# STM32F103.net
KiCad netlist of a schematic drawn in Altium Designer
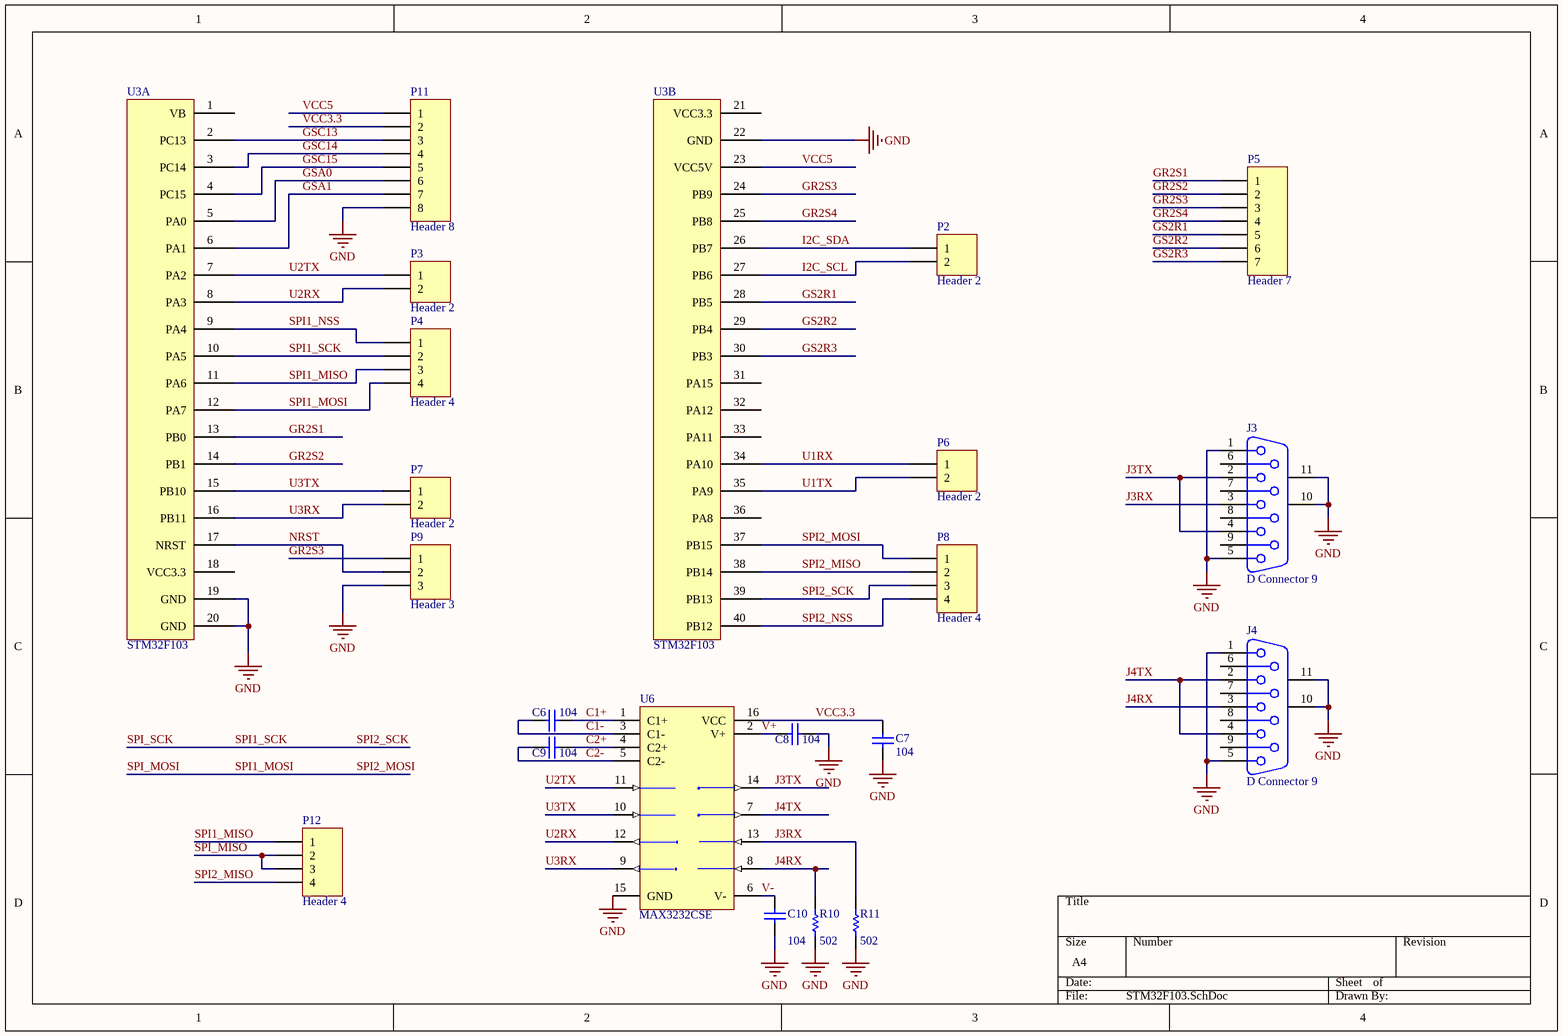
[diagram p0: STM32F103.SchDoc]

(export (version "E")
  (design (tool "Eeschema 10.0.6"))
  (components
    (comp (ref "C6")
      (value "104")
      (footprint "CAPC3216L")
      (description "Capacitor (Semiconductor SIM Model)")
      (fields (field (name "Comment") "Cap Semi") (field (name "PUBLISHER") "Altium Limited"))
      (libsource (lib "Miscellaneous Devices") (part "Cap Semi"))
    )
    (comp (ref "C7")
      (value "104")
      (footprint "CAPC3216L")
      (description "Capacitor (Semiconductor SIM Model)")
      (fields (field (name "Comment") "Cap Semi") (field (name "PUBLISHER") "Altium Limited"))
      (libsource (lib "Miscellaneous Devices") (part "Cap Semi"))
    )
    (comp (ref "C8")
      (value "104")
      (footprint "CAPC3216L")
      (description "Capacitor (Semiconductor SIM Model)")
      (fields (field (name "Comment") "Cap Semi") (field (name "PUBLISHER") "Altium Limited"))
      (libsource (lib "Miscellaneous Devices") (part "Cap Semi"))
    )
    (comp (ref "C9")
      (value "104")
      (footprint "CAPC3216L")
      (description "Capacitor (Semiconductor SIM Model)")
      (fields (field (name "Comment") "Cap Semi") (field (name "PUBLISHER") "Altium Limited"))
      (libsource (lib "Miscellaneous Devices") (part "Cap Semi"))
    )
    (comp (ref "C10")
      (value "104")
      (footprint "CAPC3216L")
      (description "Capacitor (Semiconductor SIM Model)")
      (fields (field (name "Comment") "Cap Semi") (field (name "PUBLISHER") "Altium Limited"))
      (libsource (lib "Miscellaneous Devices") (part "Cap Semi"))
    )
    (comp (ref "J3")
      (value "D Connector 9")
      (footprint "DSUB1.385-2H9")
      (description "Receptacle Assembly, 9 Position, Right Angle")
      (fields (field (name "PUBLISHER") "Altium Limited"))
      (libsource (lib "Miscellaneous Connectors") (part "D Connector 9"))
    )
    (comp (ref "J4")
      (value "D Connector 9")
      (footprint "DSUB1.385-2H9")
      (description "Receptacle Assembly, 9 Position, Right Angle")
      (fields (field (name "PUBLISHER") "Altium Limited"))
      (libsource (lib "Miscellaneous Connectors") (part "D Connector 9"))
    )
    (comp (ref "P2")
      (value "Header 2")
      (footprint "HDR1X2")
      (description "Header, 2-Pin")
      (fields (field (name "PUBLISHER") "Altium Limited"))
      (libsource (lib "Miscellaneous Connectors") (part "Header 2"))
    )
    (comp (ref "P3")
      (value "Header 2")
      (footprint "HDR1X2")
      (description "Header, 2-Pin")
      (fields (field (name "PUBLISHER") "Altium Limited"))
      (libsource (lib "Miscellaneous Connectors") (part "Header 2"))
    )
    (comp (ref "P4")
      (value "Header 4")
      (footprint "HDR1X4")
      (description "Header, 4-Pin")
      (fields (field (name "PUBLISHER") "Altium Limited"))
      (libsource (lib "Miscellaneous Connectors") (part "Header 4"))
    )
    (comp (ref "P5")
      (value "Header 7")
      (footprint "HDR1X7")
      (description "Header, 7-Pin")
      (fields (field (name "PUBLISHER") "Altium Limited"))
      (libsource (lib "Miscellaneous Connectors") (part "Header 7"))
    )
    (comp (ref "P6")
      (value "Header 2")
      (footprint "HDR1X2")
      (description "Header, 2-Pin")
      (fields (field (name "PUBLISHER") "Altium Limited"))
      (libsource (lib "Miscellaneous Connectors") (part "Header 2"))
    )
    (comp (ref "P7")
      (value "Header 2")
      (footprint "HDR1X2")
      (description "Header, 2-Pin")
      (fields (field (name "PUBLISHER") "Altium Limited"))
      (libsource (lib "Miscellaneous Connectors") (part "Header 2"))
    )
    (comp (ref "P8")
      (value "Header 4")
      (footprint "HDR1X4")
      (description "Header, 4-Pin")
      (fields (field (name "PUBLISHER") "Altium Limited"))
      (libsource (lib "Miscellaneous Connectors") (part "Header 4"))
    )
    (comp (ref "P9")
      (value "Header 3")
      (footprint "HDR1X3")
      (description "Header, 3-Pin")
      (fields (field (name "PUBLISHER") "Altium Limited"))
      (libsource (lib "Miscellaneous Connectors") (part "Header 3"))
    )
    (comp (ref "P11")
      (value "Header 8")
      (footprint "HDR1X8")
      (description "Header, 8-Pin")
      (fields (field (name "PUBLISHER") "Altium Limited"))
      (libsource (lib "Miscellaneous Connectors") (part "Header 8"))
    )
    (comp (ref "P12")
      (value "Header 4")
      (footprint "HDR1X4")
      (description "Header, 4-Pin")
      (fields (field (name "PUBLISHER") "Altium Limited"))
      (libsource (lib "Miscellaneous Connectors") (part "Header 4"))
    )
    (comp (ref "R10")
      (value "502")
      (footprint "RESC3216L")
      (description "Semiconductor Resistor")
      (fields (field (name "Comment") "Res Semi") (field (name "PUBLISHER") "Altium Limited"))
      (libsource (lib "Miscellaneous Devices") (part "Res Semi"))
    )
    (comp (ref "R11")
      (value "502")
      (footprint "RESC3216L")
      (description "Semiconductor Resistor")
      (fields (field (name "Comment") "Res Semi") (field (name "PUBLISHER") "Altium Limited"))
      (libsource (lib "Miscellaneous Devices") (part "Res Semi"))
    )
    (comp (ref "U3")
      (value "STM32F103")
      (footprint "STM32F103C8T6")
      (libsource (lib "CHK-I") (part "STM32F103C8T6"))
    )
    (comp (ref "U6")
      (value "MAX3232CSE")
      (footprint "NSO16_N")
      (description "3.0V TO 5.5V, Low-Power, up to 1Mbps, True RS-232 Transceiver Using Four 0.1µF External Capacitor")
      (fields (field (name "PUBLISHER") "Altium Limited"))
      (libsource (lib "Maxim Communication Transceiver") (part "MAX3232CSE"))
    )
  )
  (nets
    (net (code "1") (name "/C1+") (class "Default")
      (node (ref "C6") (pin "1") (pinfunction "1_1") (pintype "passive"))
      (node (ref "U6") (pin "1") (pinfunction "C1+_1") (pintype "passive"))
    )
    (net (code "2") (name "/C1-") (class "Default")
      (node (ref "C6") (pin "2") (pinfunction "2_2") (pintype "passive"))
      (node (ref "U6") (pin "3") (pinfunction "C1-_3") (pintype "passive"))
    )
    (net (code "3") (name "/C2+") (class "Default")
      (node (ref "C9") (pin "1") (pinfunction "1_1") (pintype "passive"))
      (node (ref "U6") (pin "4") (pinfunction "C2+_4") (pintype "passive"))
    )
    (net (code "4") (name "/C2-") (class "Default")
      (node (ref "C9") (pin "2") (pinfunction "2_2") (pintype "passive"))
      (node (ref "U6") (pin "5") (pinfunction "C2-_5") (pintype "passive"))
    )
    (net (code "5") (name "/GR2S1") (class "Default")
      (node (ref "P5") (pin "1") (pinfunction "1_1") (pintype "passive"))
      (node (ref "U3") (pin "13") (pinfunction "PB0_13") (pintype "passive"))
    )
    (net (code "6") (name "/GR2S2") (class "Default")
      (node (ref "P5") (pin "2") (pinfunction "2_2") (pintype "passive"))
      (node (ref "U3") (pin "14") (pinfunction "PB1_14") (pintype "passive"))
    )
    (net (code "7") (name "/GR2S3") (class "Default")
      (node (ref "P5") (pin "3") (pinfunction "3_3") (pintype "passive"))
      (node (ref "P9") (pin "1") (pinfunction "1_1") (pintype "passive"))
      (node (ref "U3") (pin "24") (pinfunction "PB9_24") (pintype "passive"))
    )
    (net (code "8") (name "/GR2S4") (class "Default")
      (node (ref "P5") (pin "4") (pinfunction "4_4") (pintype "passive"))
      (node (ref "U3") (pin "25") (pinfunction "PB8_25") (pintype "passive"))
    )
    (net (code "9") (name "/GS2R1") (class "Default")
      (node (ref "P5") (pin "5") (pinfunction "5_5") (pintype "passive"))
      (node (ref "U3") (pin "28") (pinfunction "PB5_28") (pintype "passive"))
    )
    (net (code "10") (name "/GS2R2") (class "Default")
      (node (ref "P5") (pin "6") (pinfunction "6_6") (pintype "passive"))
      (node (ref "U3") (pin "29") (pinfunction "PB4_29") (pintype "passive"))
    )
    (net (code "11") (name "/GS2R3") (class "Default")
      (node (ref "P5") (pin "7") (pinfunction "7_7") (pintype "passive"))
      (node (ref "U3") (pin "30") (pinfunction "PB3_30") (pintype "passive"))
    )
    (net (code "12") (name "/GSA0") (class "Default")
      (node (ref "P11") (pin "6") (pinfunction "6_6") (pintype "passive"))
      (node (ref "U3") (pin "5") (pinfunction "PA0_5") (pintype "passive"))
    )
    (net (code "13") (name "/GSA1") (class "Default")
      (node (ref "P11") (pin "7") (pinfunction "7_7") (pintype "passive"))
      (node (ref "U3") (pin "6") (pinfunction "PA1_6") (pintype "passive"))
    )
    (net (code "14") (name "/GSC13") (class "Default")
      (node (ref "P11") (pin "3") (pinfunction "3_3") (pintype "passive"))
      (node (ref "U3") (pin "2") (pinfunction "PC13_2") (pintype "passive"))
    )
    (net (code "15") (name "/GSC14") (class "Default")
      (node (ref "P11") (pin "4") (pinfunction "4_4") (pintype "passive"))
      (node (ref "U3") (pin "3") (pinfunction "PC14_3") (pintype "passive"))
    )
    (net (code "16") (name "/GSC15") (class "Default")
      (node (ref "P11") (pin "5") (pinfunction "5_5") (pintype "passive"))
      (node (ref "U3") (pin "4") (pinfunction "PC15_4") (pintype "passive"))
    )
    (net (code "17") (name "/I2C_SCL") (class "Default")
      (node (ref "P2") (pin "2") (pinfunction "2_2") (pintype "passive"))
      (node (ref "U3") (pin "27") (pinfunction "PB6_27") (pintype "passive"))
    )
    (net (code "18") (name "/I2C_SDA") (class "Default")
      (node (ref "P2") (pin "1") (pinfunction "1_1") (pintype "passive"))
      (node (ref "U3") (pin "26") (pinfunction "PB7_26") (pintype "passive"))
    )
    (net (code "19") (name "/J3RX") (class "Default")
      (node (ref "J3") (pin "3") (pinfunction "3_3") (pintype "passive"))
      (node (ref "R11") (pin "2") (pinfunction "2_2") (pintype "passive"))
      (node (ref "U6") (pin "13") (pinfunction "R1IN_13") (pintype "input"))
    )
    (net (code "20") (name "/J3TX") (class "Default")
      (node (ref "J3") (pin "2") (pinfunction "2_2") (pintype "passive"))
      (node (ref "J3") (pin "4") (pinfunction "4_4") (pintype "passive"))
      (node (ref "U6") (pin "14") (pinfunction "T1OUT_14") (pintype "output"))
    )
    (net (code "21") (name "/J4RX") (class "Default")
      (node (ref "J4") (pin "3") (pinfunction "3_3") (pintype "passive"))
      (node (ref "R10") (pin "2") (pinfunction "2_2") (pintype "passive"))
      (node (ref "U6") (pin "8") (pinfunction "R2IN_8") (pintype "input"))
    )
    (net (code "22") (name "/J4TX") (class "Default")
      (node (ref "J4") (pin "2") (pinfunction "2_2") (pintype "passive"))
      (node (ref "J4") (pin "4") (pinfunction "4_4") (pintype "passive"))
      (node (ref "U6") (pin "7") (pinfunction "T2OUT_7") (pintype "output"))
    )
    (net (code "23") (name "/NRST") (class "Default")
      (node (ref "P9") (pin "2") (pinfunction "2_2") (pintype "passive"))
      (node (ref "U3") (pin "17") (pinfunction "NRST_17") (pintype "passive"))
    )
    (net (code "24") (name "/SPI1_MISO") (class "Default")
      (node (ref "P12") (pin "1") (pinfunction "1_1") (pintype "passive"))
      (node (ref "P4") (pin "3") (pinfunction "3_3") (pintype "passive"))
      (node (ref "U3") (pin "11") (pinfunction "PA6_11") (pintype "passive"))
    )
    (net (code "25") (name "/SPI1_MOSI") (class "Default")
      (node (ref "P4") (pin "4") (pinfunction "4_4") (pintype "passive"))
      (node (ref "P8") (pin "1") (pinfunction "1_1") (pintype "passive"))
      (node (ref "U3") (pin "12") (pinfunction "PA7_12") (pintype "passive"))
      (node (ref "U3") (pin "37") (pinfunction "PB15_37") (pintype "passive"))
    )
    (net (code "26") (name "/SPI1_NSS") (class "Default")
      (node (ref "P4") (pin "1") (pinfunction "1_1") (pintype "passive"))
      (node (ref "U3") (pin "9") (pinfunction "PA4_9") (pintype "passive"))
    )
    (net (code "27") (name "/SPI1_SCK") (class "Default")
      (node (ref "P4") (pin "2") (pinfunction "2_2") (pintype "passive"))
      (node (ref "P8") (pin "3") (pinfunction "3_3") (pintype "passive"))
      (node (ref "U3") (pin "10") (pinfunction "PA5_10") (pintype "passive"))
      (node (ref "U3") (pin "39") (pinfunction "PB13_39") (pintype "passive"))
    )
    (net (code "28") (name "/SPI2_MISO") (class "Default")
      (node (ref "P12") (pin "4") (pinfunction "4_4") (pintype "passive"))
      (node (ref "P8") (pin "2") (pinfunction "2_2") (pintype "passive"))
      (node (ref "U3") (pin "38") (pinfunction "PB14_38") (pintype "passive"))
    )
    (net (code "29") (name "/SPI2_NSS") (class "Default")
      (node (ref "P8") (pin "4") (pinfunction "4_4") (pintype "passive"))
      (node (ref "U3") (pin "40") (pinfunction "PB12_40") (pintype "passive"))
    )
    (net (code "30") (name "/SPI_MISO") (class "Default")
      (node (ref "P12") (pin "2") (pinfunction "2_2") (pintype "passive"))
      (node (ref "P12") (pin "3") (pinfunction "3_3") (pintype "passive"))
    )
    (net (code "31") (name "/U1RX") (class "Default")
      (node (ref "P6") (pin "1") (pinfunction "1_1") (pintype "passive"))
      (node (ref "U3") (pin "34") (pinfunction "PA10_34") (pintype "passive"))
    )
    (net (code "32") (name "/U1TX") (class "Default")
      (node (ref "P6") (pin "2") (pinfunction "2_2") (pintype "passive"))
      (node (ref "U3") (pin "35") (pinfunction "PA9_35") (pintype "passive"))
    )
    (net (code "33") (name "/U2RX") (class "Default")
      (node (ref "P3") (pin "2") (pinfunction "2_2") (pintype "passive"))
      (node (ref "U3") (pin "8") (pinfunction "PA3_8") (pintype "passive"))
      (node (ref "U6") (pin "12") (pinfunction "R1OUT_12") (pintype "output"))
    )
    (net (code "34") (name "/U2TX") (class "Default")
      (node (ref "P3") (pin "1") (pinfunction "1_1") (pintype "passive"))
      (node (ref "U3") (pin "7") (pinfunction "PA2_7") (pintype "passive"))
      (node (ref "U6") (pin "11") (pinfunction "T1IN_11") (pintype "input"))
    )
    (net (code "35") (name "/U3RX") (class "Default")
      (node (ref "P7") (pin "2") (pinfunction "2_2") (pintype "passive"))
      (node (ref "U3") (pin "16") (pinfunction "PB11_16") (pintype "passive"))
      (node (ref "U6") (pin "9") (pinfunction "R2OUT_9") (pintype "output"))
    )
    (net (code "36") (name "/U3TX") (class "Default")
      (node (ref "P7") (pin "1") (pinfunction "1_1") (pintype "passive"))
      (node (ref "U3") (pin "15") (pinfunction "PB10_15") (pintype "passive"))
      (node (ref "U6") (pin "10") (pinfunction "T2IN_10") (pintype "input"))
    )
    (net (code "37") (name "/V+") (class "Default")
      (node (ref "C8") (pin "2") (pinfunction "2_2") (pintype "passive"))
      (node (ref "U6") (pin "2") (pinfunction "V+_2") (pintype "power_in"))
    )
    (net (code "38") (name "/V-") (class "Default")
      (node (ref "C10") (pin "2") (pinfunction "2_2") (pintype "passive"))
      (node (ref "U6") (pin "6") (pinfunction "V-_6") (pintype "power_in"))
    )
    (net (code "39") (name "/VCC3.3") (class "Default")
      (node (ref "C7") (pin "1") (pinfunction "1_1") (pintype "passive"))
      (node (ref "P11") (pin "2") (pinfunction "2_2") (pintype "passive"))
      (node (ref "U6") (pin "16") (pinfunction "VCC_16") (pintype "power_in"))
    )
    (net (code "40") (name "/VCC5") (class "Default")
      (node (ref "P11") (pin "1") (pinfunction "1_1") (pintype "passive"))
      (node (ref "U3") (pin "23") (pinfunction "VCC5V_23") (pintype "passive"))
    )
    (net (code "41") (name "GND") (class "Default")
      (node (ref "C10") (pin "1") (pinfunction "1_1") (pintype "passive"))
      (node (ref "C7") (pin "2") (pinfunction "2_2") (pintype "passive"))
      (node (ref "C8") (pin "1") (pinfunction "1_1") (pintype "passive"))
      (node (ref "J3") (pin "1") (pinfunction "1_1") (pintype "passive"))
      (node (ref "J3") (pin "10") (pinfunction "MH1_10") (pintype "passive"))
      (node (ref "J3") (pin "11") (pinfunction "MH2_11") (pintype "passive"))
      (node (ref "J3") (pin "5") (pinfunction "5_5") (pintype "passive"))
      (node (ref "J4") (pin "1") (pinfunction "1_1") (pintype "passive"))
      (node (ref "J4") (pin "10") (pinfunction "MH1_10") (pintype "passive"))
      (node (ref "J4") (pin "11") (pinfunction "MH2_11") (pintype "passive"))
      (node (ref "J4") (pin "5") (pinfunction "5_5") (pintype "passive"))
      (node (ref "P11") (pin "8") (pinfunction "8_8") (pintype "passive"))
      (node (ref "P9") (pin "3") (pinfunction "3_3") (pintype "passive"))
      (node (ref "R10") (pin "1") (pinfunction "1_1") (pintype "passive"))
      (node (ref "R11") (pin "1") (pinfunction "1_1") (pintype "passive"))
      (node (ref "U3") (pin "19") (pinfunction "GND_19") (pintype "passive"))
      (node (ref "U3") (pin "20") (pinfunction "GND_20") (pintype "passive"))
      (node (ref "U3") (pin "22") (pinfunction "GND_22") (pintype "passive"))
      (node (ref "U6") (pin "15") (pinfunction "GND_15") (pintype "power_in"))
    )
    (net (code "42") (name "unconnected-(J3-Pad6)") (class "Default")
      (node (ref "J3") (pin "6") (pinfunction "6_6") (pintype "passive"))
    )
    (net (code "43") (name "unconnected-(J3-Pad7)") (class "Default")
      (node (ref "J3") (pin "7") (pinfunction "7_7") (pintype "passive"))
    )
    (net (code "44") (name "unconnected-(J3-Pad8)") (class "Default")
      (node (ref "J3") (pin "8") (pinfunction "8_8") (pintype "passive"))
    )
    (net (code "45") (name "unconnected-(J3-Pad9)") (class "Default")
      (node (ref "J3") (pin "9") (pinfunction "9_9") (pintype "passive"))
    )
    (net (code "46") (name "unconnected-(J4-Pad6)") (class "Default")
      (node (ref "J4") (pin "6") (pinfunction "6_6") (pintype "passive"))
    )
    (net (code "47") (name "unconnected-(J4-Pad7)") (class "Default")
      (node (ref "J4") (pin "7") (pinfunction "7_7") (pintype "passive"))
    )
    (net (code "48") (name "unconnected-(J4-Pad8)") (class "Default")
      (node (ref "J4") (pin "8") (pinfunction "8_8") (pintype "passive"))
    )
    (net (code "49") (name "unconnected-(J4-Pad9)") (class "Default")
      (node (ref "J4") (pin "9") (pinfunction "9_9") (pintype "passive"))
    )
    (net (code "50") (name "unconnected-(U3A-VB-Pad1)") (class "Default")
      (node (ref "U3") (pin "1") (pinfunction "VB_1") (pintype "passive"))
    )
    (net (code "51") (name "unconnected-(U3A-VCC3.3-Pad18)") (class "Default")
      (node (ref "U3") (pin "18") (pinfunction "VCC3.3_18") (pintype "passive"))
    )
    (net (code "52") (name "unconnected-(U3B-PA8-Pad36)") (class "Default")
      (node (ref "U3") (pin "36") (pinfunction "PA8_36") (pintype "passive"))
    )
    (net (code "53") (name "unconnected-(U3B-PA11-Pad33)") (class "Default")
      (node (ref "U3") (pin "33") (pinfunction "PA11_33") (pintype "passive"))
    )
    (net (code "54") (name "unconnected-(U3B-PA12-Pad32)") (class "Default")
      (node (ref "U3") (pin "32") (pinfunction "PA12_32") (pintype "passive"))
    )
    (net (code "55") (name "unconnected-(U3B-PA15-Pad31)") (class "Default")
      (node (ref "U3") (pin "31") (pinfunction "PA15_31") (pintype "passive"))
    )
    (net (code "56") (name "unconnected-(U3B-VCC3.3-Pad21)") (class "Default")
      (node (ref "U3") (pin "21") (pinfunction "VCC3.3_21") (pintype "passive"))
    )
  )
)
